# BLDC_Gimbal_Top.net
KiCad netlist of a schematic drawn in Altium Designer
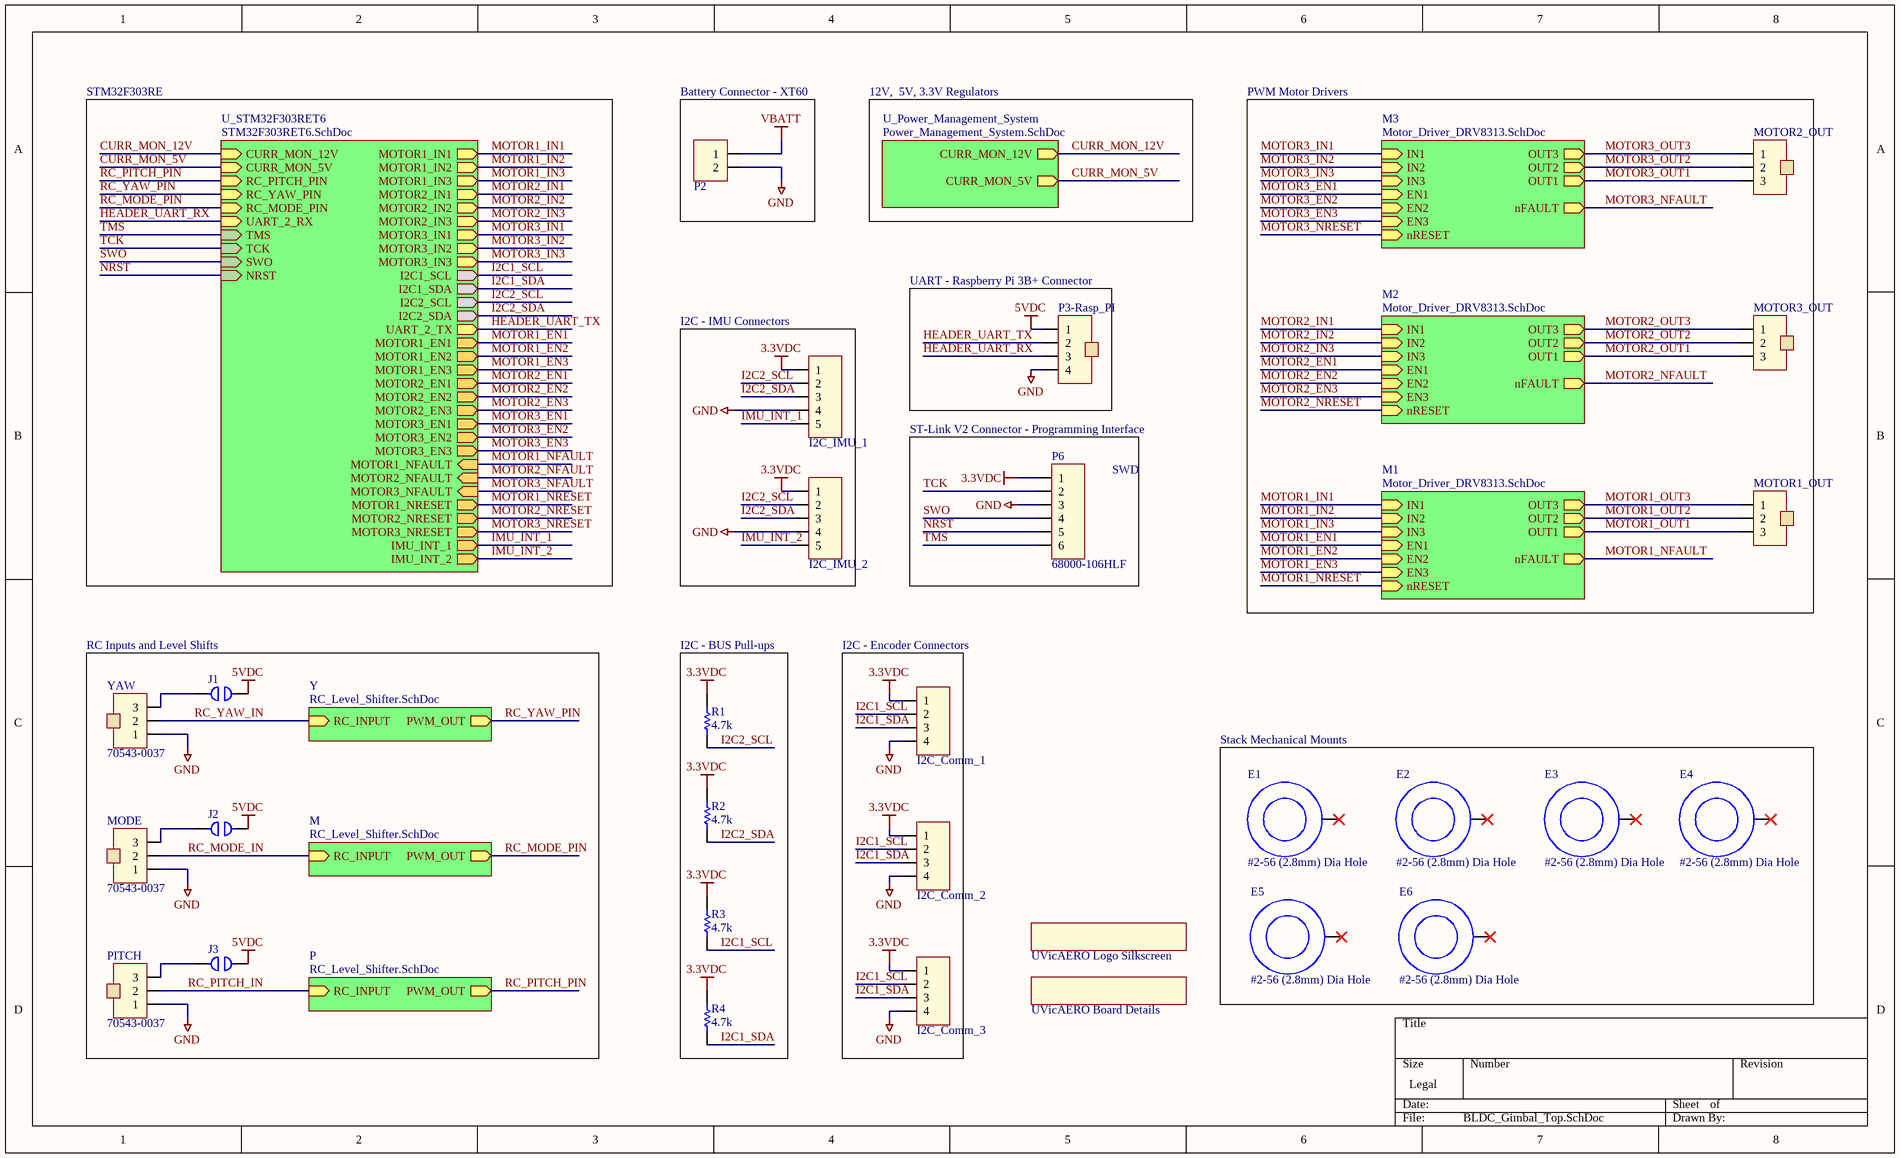
[diagram p0: BLDC_Gimbal_Top.SchDoc]

(export (version "E")
  (design (tool "Eeschema 10.0.6"))
  (components
    (comp (ref "E1")
      (value "#2-56 (2.8mm) Dia Hole")
      (footprint "2-56, Mounting Hole")
      (description "#2-56, with Pin, Mounting Hole")
      (fields (field (name "PUBLISHER") "UVic AERO, KCMR"))
      (libsource (lib "AERO Integrated Library - Miscellaneous") (part "#2-56, w-Pin, Mounting Hole"))
    )
    (comp (ref "E2")
      (value "#2-56 (2.8mm) Dia Hole")
      (footprint "2-56, Mounting Hole")
      (description "#2-56, with Pin, Mounting Hole")
      (fields (field (name "PUBLISHER") "UVic AERO, KCMR"))
      (libsource (lib "AERO Integrated Library - Miscellaneous") (part "#2-56, w-Pin, Mounting Hole"))
    )
    (comp (ref "E3")
      (value "#2-56 (2.8mm) Dia Hole")
      (footprint "2-56, Mounting Hole")
      (description "#2-56, with Pin, Mounting Hole")
      (fields (field (name "PUBLISHER") "UVic AERO, KCMR"))
      (libsource (lib "AERO Integrated Library - Miscellaneous") (part "#2-56, w-Pin, Mounting Hole"))
    )
    (comp (ref "E4")
      (value "#2-56 (2.8mm) Dia Hole")
      (footprint "2-56, Mounting Hole")
      (description "#2-56, with Pin, Mounting Hole")
      (fields (field (name "PUBLISHER") "UVic AERO, KCMR"))
      (libsource (lib "AERO Integrated Library - Miscellaneous") (part "#2-56, w-Pin, Mounting Hole"))
    )
    (comp (ref "E5")
      (value "#2-56 (2.8mm) Dia Hole")
      (footprint "2-56, Mounting Hole")
      (description "#2-56, with Pin, Mounting Hole")
      (fields (field (name "PUBLISHER") "UVic AERO, KCMR"))
      (libsource (lib "AERO Integrated Library - Miscellaneous") (part "#2-56, w-Pin, Mounting Hole"))
    )
    (comp (ref "E6")
      (value "#2-56 (2.8mm) Dia Hole")
      (footprint "2-56, Mounting Hole")
      (description "#2-56, with Pin, Mounting Hole")
      (fields (field (name "PUBLISHER") "UVic AERO, KCMR"))
      (libsource (lib "AERO Integrated Library - Miscellaneous") (part "#2-56, w-Pin, Mounting Hole"))
    )
    (comp (ref "I2C_Comm_1")
      (value "B4B-ZR-SM4-TF(LF)(SN)")
      (footprint "1x4-PIN ZH 1.5mm Pitch")
      (description "Conn Shrouded Header HDR 4 POS 1.5mm Solder ST SMD T/R")
      (fields (field (name "MANUFACTURER") "JST"))
      (libsource (lib "BLDC_Gimbal_Prototype_Lib") (part "B4B-ZR-SM4-TF(LF)(SN)"))
    )
    (comp (ref "I2C_Comm_2")
      (value "B4B-ZR-SM4-TF(LF)(SN)")
      (footprint "1x4-PIN ZH 1.5mm Pitch")
      (description "Conn Shrouded Header HDR 4 POS 1.5mm Solder ST SMD T/R")
      (fields (field (name "MANUFACTURER") "JST"))
      (libsource (lib "BLDC_Gimbal_Prototype_Lib") (part "B4B-ZR-SM4-TF(LF)(SN)"))
    )
    (comp (ref "I2C_Comm_3")
      (value "B4B-ZR-SM4-TF(LF)(SN)")
      (footprint "1x4-PIN ZH 1.5mm Pitch")
      (description "Conn Shrouded Header HDR 4 POS 1.5mm Solder ST SMD T/R")
      (fields (field (name "MANUFACTURER") "JST"))
      (libsource (lib "BLDC_Gimbal_Prototype_Lib") (part "B4B-ZR-SM4-TF(LF)(SN)"))
    )
    (comp (ref "I2C_IMU_1")
      (value "B5B-ZR-SM4-TF(LF)(SN)")
      (footprint "1x5-PIN ZH 1.5mm Pitch")
      (description "CONN HEADER ZH TOP 5POS 1.5MM")
      (fields (field (name "MANUFACTURER") "JST"))
      (libsource (lib "BLDC_Gimbal_Prototype_Lib") (part "B5B-ZR-SM4-TF(LF)(SN)"))
    )
    (comp (ref "I2C_IMU_2")
      (value "B5B-ZR-SM4-TF(LF)(SN)")
      (footprint "1x5-PIN ZH 1.5mm Pitch")
      (description "CONN HEADER ZH TOP 5POS 1.5MM")
      (fields (field (name "MANUFACTURER") "JST"))
      (libsource (lib "BLDC_Gimbal_Prototype_Lib") (part "B5B-ZR-SM4-TF(LF)(SN)"))
    )
    (comp (ref "J1")
      (value "3M9580-ND")
      (footprint "Jumper-2Pin, THT")
      (description "Jumper, 0.1\" (2.54mm), Gold, THT, 68001-202HLF & 3M9580-ND")
      (fields
        (field (name "MFG") "FCI")
        (field (name "PUBLISHER") "UVic AERO, Kirk Richardson")
        (field (name "REVIEWEDBY") "*")
      )
      (libsource (lib "AERO Schematic Library - Miscellaneous") (part "Jumper, 0.1{dblquote} (2.54mm), Gold, THT, 68001-202HLF"))
    )
    (comp (ref "J2")
      (value "3M9580-ND")
      (footprint "Jumper-2Pin, THT")
      (description "Jumper, 0.1\" (2.54mm), Gold, THT, 68001-202HLF & 3M9580-ND")
      (fields
        (field (name "MFG") "FCI")
        (field (name "PUBLISHER") "UVic AERO, Kirk Richardson")
        (field (name "REVIEWEDBY") "*")
      )
      (libsource (lib "AERO Schematic Library - Miscellaneous") (part "Jumper, 0.1{dblquote} (2.54mm), Gold, THT, 68001-202HLF"))
    )
    (comp (ref "J3")
      (value "3M9580-ND")
      (footprint "Jumper-2Pin, THT")
      (description "Jumper, 0.1\" (2.54mm), Gold, THT, 68001-202HLF & 3M9580-ND")
      (fields
        (field (name "MFG") "FCI")
        (field (name "PUBLISHER") "UVic AERO, Kirk Richardson")
        (field (name "REVIEWEDBY") "*")
      )
      (libsource (lib "AERO Schematic Library - Miscellaneous") (part "Jumper, 0.1{dblquote} (2.54mm), Gold, THT, 68001-202HLF"))
    )
    (comp (ref "LB1")
      (value "UVicAERO Board Details")
      (footprint "UVicAERO, Board Details, Silkscreen")
      (description "Logo, UVic AERO, Board Details, Silkscreen")
      (fields (field (name "PUBLISHER") "UVic AERO, KCMR"))
      (libsource (lib "AERO Schematic Library - Miscellaneous") (part "Logo, UVic AERO, Board Details"))
    )
    (comp (ref "LB2")
      (value "UVicAERO Logo Silkscreen")
      (footprint "UVicAERO_Logo, 7mm Width")
      (description "Logo, UVic AERO 2014, 7mm Width, Silkscreen")
      (fields (field (name "PUBLISHER") "UVic AERO, KCMR"))
      (libsource (lib "AERO Schematic Library - Miscellaneous") (part "Logo, UVic AERO 2014, 7mm"))
    )
    (comp (ref "MODE")
      (value "70543-0037")
      (footprint "Header-3Pin, THT, Shrouded")
      (description "1x3-Pin, Pitch: 0.1\" (2.54mm), Tin, THT, Shrouded, Locking, 70543-0037")
      (fields
        (field (name "MFG") "Molex Inc")
        (field (name "PUBLISHER") "UVic AERO, Kirk Richardson")
        (field (name "REVIEWEDBY") "Matthew Fitz")
        (field (name "REVIEWEDNOTE") "There should be tin pins instead of gold")
      )
      (libsource (lib "AERO Schematic Library - Connectors") (part "1x3-Pin, Pitch{colon} 0.1{dblquote} (2.54mm), Tin, THT, Shrouded, Locking, 70543-0037"))
    )
    (comp (ref "MOTOR1_OUT")
      (value "70543-0037")
      (footprint "Header-3Pin, THT, Shrouded")
      (description "1x3-Pin, Pitch: 0.1\" (2.54mm), Tin, THT, Shrouded, Locking, 70543-0037")
      (fields
        (field (name "MFG") "Molex Inc")
        (field (name "PUBLISHER") "UVic AERO, Kirk Richardson")
        (field (name "REVIEWEDBY") "Matthew Fitz")
        (field (name "REVIEWEDNOTE") "There should be tin pins instead of gold")
      )
      (libsource (lib "") (part "1x3-Pin, Pitch{colon} 0.1{dblquote} (2.54mm), Tin, THT, Shrouded, Locking, 70543-0037_1"))
    )
    (comp (ref "MOTOR2_OUT")
      (value "70543-0037")
      (footprint "Header-3Pin, THT, Shrouded")
      (description "1x3-Pin, Pitch: 0.1\" (2.54mm), Tin, THT, Shrouded, Locking, 70543-0037")
      (fields
        (field (name "MFG") "Molex Inc")
        (field (name "PUBLISHER") "UVic AERO, Kirk Richardson")
        (field (name "REVIEWEDBY") "Matthew Fitz")
        (field (name "REVIEWEDNOTE") "There should be tin pins instead of gold")
      )
      (libsource (lib "") (part "1x3-Pin, Pitch{colon} 0.1{dblquote} (2.54mm), Tin, THT, Shrouded, Locking, 70543-0037_1"))
    )
    (comp (ref "MOTOR3_OUT")
      (value "70543-0037")
      (footprint "Header-3Pin, THT, Shrouded")
      (description "1x3-Pin, Pitch: 0.1\" (2.54mm), Tin, THT, Shrouded, Locking, 70543-0037")
      (fields
        (field (name "MFG") "Molex Inc")
        (field (name "PUBLISHER") "UVic AERO, Kirk Richardson")
        (field (name "REVIEWEDBY") "Matthew Fitz")
        (field (name "REVIEWEDNOTE") "There should be tin pins instead of gold")
      )
      (libsource (lib "") (part "1x3-Pin, Pitch{colon} 0.1{dblquote} (2.54mm), Tin, THT, Shrouded, Locking, 70543-0037_1"))
    )
    (comp (ref "P2")
      (value "2x1-Pin, Pitch: 3.00mm, Battery Connector")
      (footprint "XT60")
      (description "XT60 - 2x1-Pin, Pitch: 3.00mm, Battery Connector")
      (fields (field (name "PUBLISHER") "UVic AERO, Luke Mills") (field (name "REVIEWEDBY") "*"))
      (libsource (lib "BLDC_Gimbal_Lib") (part "2x1-Pin, Pitch{colon} 3.00mm, Battery Connector"))
    )
    (comp (ref "P3-Rasp_PI")
      (value "43045-0412")
      (footprint "Header-4Pin, 2x2, THT, Locking, Tin")
      (description "2x2-Pin, Pitch: 3.00mm, Tin, THT, Shrouded, Locking, 43045-0412")
      (fields
        (field (name "MFG") "Molex")
        (field (name "PUBLISHER") "UVic AERO, Taylor Eby")
        (field (name "REVIEWEDBY") "Kirk Richardson")
      )
      (libsource (lib "AERO Schematic Library - Connectors") (part "2x2-Pin, Pitch{colon} 3.00mm, Tin, THT, 43045-0412"))
    )
    (comp (ref "P6")
      (value "68000-106HLF")
      (footprint "Header-6Pin, THT")
      (description "Header, 1x6-Pin, Pitch: 0.1\" (2.54mm), Gold 30µin, THT, 68000-106HLF")
      (fields
        (field (name "MFG") "FCI")
        (field (name "PUBLISHER") "UVic AERO, Kirk Richardson")
        (field (name "REVIEWEDBY") "*")
      )
      (libsource (lib "AERO Integrated Library - Connectors") (part "Header, 1x6-Pin, Pitch{colon} 0.1{dblquote} (2.54mm), Gold 30µin, THT, 68000-106HLF"))
    )
    (comp (ref "PITCH")
      (value "70543-0037")
      (footprint "Header-3Pin, THT, Shrouded")
      (description "1x3-Pin, Pitch: 0.1\" (2.54mm), Tin, THT, Shrouded, Locking, 70543-0037")
      (fields
        (field (name "MFG") "Molex Inc")
        (field (name "PUBLISHER") "UVic AERO, Kirk Richardson")
        (field (name "REVIEWEDBY") "Matthew Fitz")
        (field (name "REVIEWEDNOTE") "There should be tin pins instead of gold")
      )
      (libsource (lib "AERO Schematic Library - Connectors") (part "1x3-Pin, Pitch{colon} 0.1{dblquote} (2.54mm), Tin, THT, Shrouded, Locking, 70543-0037"))
    )
    (comp (ref "R1")
      (value "4.7k")
      (footprint "RESC2012N(0805\")")
      (description "RES SMD 4.7k ohm, 150 V, 0805 [2012 Metric], 250 mW,  1%")
      (fields
        (field (name "MANUFACTURER") "Yageo")
        (field (name "MANUFACTURER PART NUMBER") "RC0805FR-074K7L")
      )
      (libsource (lib "BLDC_Gimbal_Prototype_Lib") (part "RC0805FR-074K7L"))
    )
    (comp (ref "R2")
      (value "4.7k")
      (footprint "RESC2012N(0805\")")
      (description "RES SMD 4.7k ohm, 150 V, 0805 [2012 Metric], 250 mW,  1%")
      (fields
        (field (name "MANUFACTURER") "Yageo")
        (field (name "MANUFACTURER PART NUMBER") "RC0805FR-074K7L")
      )
      (libsource (lib "BLDC_Gimbal_Prototype_Lib") (part "RC0805FR-074K7L"))
    )
    (comp (ref "R3")
      (value "4.7k")
      (footprint "RESC2012N(0805\")")
      (description "RES SMD 4.7k ohm, 150 V, 0805 [2012 Metric], 250 mW,  1%")
      (fields
        (field (name "MANUFACTURER") "Yageo")
        (field (name "MANUFACTURER PART NUMBER") "RC0805FR-074K7L")
      )
      (libsource (lib "BLDC_Gimbal_Prototype_Lib") (part "RC0805FR-074K7L"))
    )
    (comp (ref "R4")
      (value "4.7k")
      (footprint "RESC2012N(0805\")")
      (description "RES SMD 4.7k ohm, 150 V, 0805 [2012 Metric], 250 mW,  1%")
      (fields
        (field (name "MANUFACTURER") "Yageo")
        (field (name "MANUFACTURER PART NUMBER") "RC0805FR-074K7L")
      )
      (libsource (lib "BLDC_Gimbal_Prototype_Lib") (part "RC0805FR-074K7L"))
    )
    (comp (ref "YAW")
      (value "70543-0037")
      (footprint "Header-3Pin, THT, Shrouded")
      (description "1x3-Pin, Pitch: 0.1\" (2.54mm), Tin, THT, Shrouded, Locking, 70543-0037")
      (fields
        (field (name "MFG") "Molex Inc")
        (field (name "PUBLISHER") "UVic AERO, Kirk Richardson")
        (field (name "REVIEWEDBY") "Matthew Fitz")
        (field (name "REVIEWEDNOTE") "There should be tin pins instead of gold")
      )
      (libsource (lib "AERO Schematic Library - Connectors") (part "1x3-Pin, Pitch{colon} 0.1{dblquote} (2.54mm), Tin, THT, Shrouded, Locking, 70543-0037"))
    )
  )
  (nets
    (net (code "3") (name "/HEADER_UART_RX") (class "Default")
      (node (ref "P3-Rasp_PI") (pin "3") (pinfunction "3_3") (pintype "passive"))
    )
    (net (code "4") (name "/HEADER_UART_TX") (class "Default")
      (node (ref "P3-Rasp_PI") (pin "2") (pinfunction "2_2") (pintype "passive"))
    )
    (net (code "5") (name "/I2C1_SCL") (class "Default")
      (node (ref "I2C_Comm_1") (pin "2") (pinfunction "2_2") (pintype "passive"))
      (node (ref "I2C_Comm_2") (pin "2") (pinfunction "2_2") (pintype "passive"))
      (node (ref "I2C_Comm_3") (pin "2") (pinfunction "2_2") (pintype "passive"))
      (node (ref "R3") (pin "1") (pinfunction "1_1") (pintype "passive"))
    )
    (net (code "6") (name "/I2C1_SDA") (class "Default")
      (node (ref "I2C_Comm_1") (pin "3") (pinfunction "3_3") (pintype "passive"))
      (node (ref "I2C_Comm_2") (pin "3") (pinfunction "3_3") (pintype "passive"))
      (node (ref "I2C_Comm_3") (pin "3") (pinfunction "3_3") (pintype "passive"))
      (node (ref "R4") (pin "1") (pinfunction "1_1") (pintype "passive"))
    )
    (net (code "7") (name "/I2C2_SCL") (class "Default")
      (node (ref "I2C_IMU_1") (pin "2") (pinfunction "2_2") (pintype "passive"))
      (node (ref "I2C_IMU_2") (pin "2") (pinfunction "2_2") (pintype "passive"))
      (node (ref "R1") (pin "1") (pinfunction "1_1") (pintype "passive"))
    )
    (net (code "8") (name "/I2C2_SDA") (class "Default")
      (node (ref "I2C_IMU_1") (pin "3") (pinfunction "3_3") (pintype "passive"))
      (node (ref "I2C_IMU_2") (pin "3") (pinfunction "3_3") (pintype "passive"))
      (node (ref "R2") (pin "1") (pinfunction "1_1") (pintype "passive"))
    )
    (net (code "9") (name "/IMU_INT_1") (class "Default")
      (node (ref "I2C_IMU_1") (pin "5") (pinfunction "5_5") (pintype "passive"))
    )
    (net (code "10") (name "/IMU_INT_2") (class "Default")
      (node (ref "I2C_IMU_2") (pin "5") (pinfunction "5_5") (pintype "passive"))
    )
    (net (code "19") (name "/MOTOR1_OUT1") (class "Default")
      (node (ref "MOTOR1_OUT") (pin "3") (pinfunction "3_3") (pintype "passive"))
    )
    (net (code "20") (name "/MOTOR1_OUT2") (class "Default")
      (node (ref "MOTOR1_OUT") (pin "2") (pinfunction "2_2") (pintype "passive"))
    )
    (net (code "21") (name "/MOTOR1_OUT3") (class "Default")
      (node (ref "MOTOR1_OUT") (pin "1") (pinfunction "1_1") (pintype "passive"))
    )
    (net (code "30") (name "/MOTOR2_OUT1") (class "Default")
      (node (ref "MOTOR3_OUT") (pin "3") (pinfunction "3_3") (pintype "passive"))
    )
    (net (code "31") (name "/MOTOR2_OUT2") (class "Default")
      (node (ref "MOTOR3_OUT") (pin "2") (pinfunction "2_2") (pintype "passive"))
    )
    (net (code "32") (name "/MOTOR2_OUT3") (class "Default")
      (node (ref "MOTOR3_OUT") (pin "1") (pinfunction "1_1") (pintype "passive"))
    )
    (net (code "41") (name "/MOTOR3_OUT1") (class "Default")
      (node (ref "MOTOR2_OUT") (pin "3") (pinfunction "3_3") (pintype "passive"))
    )
    (net (code "42") (name "/MOTOR3_OUT2") (class "Default")
      (node (ref "MOTOR2_OUT") (pin "2") (pinfunction "2_2") (pintype "passive"))
    )
    (net (code "43") (name "/MOTOR3_OUT3") (class "Default")
      (node (ref "MOTOR2_OUT") (pin "1") (pinfunction "1_1") (pintype "passive"))
    )
    (net (code "44") (name "/NRST") (class "Default")
      (node (ref "P6") (pin "5") (pinfunction "5_5") (pintype "passive"))
    )
    (net (code "45") (name "/RC_MODE_IN") (class "Default")
      (node (ref "MODE") (pin "2") (pinfunction "2_2") (pintype "passive"))
    )
    (net (code "47") (name "/RC_PITCH_IN") (class "Default")
      (node (ref "PITCH") (pin "2") (pinfunction "2_2") (pintype "passive"))
    )
    (net (code "49") (name "/RC_YAW_IN") (class "Default")
      (node (ref "YAW") (pin "2") (pinfunction "2_2") (pintype "passive"))
    )
    (net (code "51") (name "/SWO") (class "Default")
      (node (ref "P6") (pin "4") (pinfunction "4_4") (pintype "passive"))
    )
    (net (code "52") (name "/TCK") (class "Default")
      (node (ref "P6") (pin "2") (pinfunction "2_2") (pintype "passive"))
    )
    (net (code "53") (name "/TMS") (class "Default")
      (node (ref "P6") (pin "6") (pinfunction "6_6") (pintype "passive"))
    )
    (net (code "54") (name "3.3VDC") (class "Default")
      (node (ref "I2C_Comm_1") (pin "1") (pinfunction "1_1") (pintype "passive"))
      (node (ref "I2C_Comm_2") (pin "1") (pinfunction "1_1") (pintype "passive"))
      (node (ref "I2C_Comm_3") (pin "1") (pinfunction "1_1") (pintype "passive"))
      (node (ref "I2C_IMU_1") (pin "1") (pinfunction "1_1") (pintype "passive"))
      (node (ref "I2C_IMU_2") (pin "1") (pinfunction "1_1") (pintype "passive"))
      (node (ref "P6") (pin "1") (pinfunction "1_1") (pintype "passive"))
      (node (ref "R1") (pin "2") (pinfunction "2_2") (pintype "passive"))
      (node (ref "R2") (pin "2") (pinfunction "2_2") (pintype "passive"))
      (node (ref "R3") (pin "2") (pinfunction "2_2") (pintype "passive"))
      (node (ref "R4") (pin "2") (pinfunction "2_2") (pintype "passive"))
    )
    (net (code "55") (name "5VDC") (class "Default")
      (node (ref "J1") (pin "2") (pinfunction "2_2") (pintype "passive"))
      (node (ref "J2") (pin "2") (pinfunction "2_2") (pintype "passive"))
      (node (ref "J3") (pin "2") (pinfunction "2_2") (pintype "passive"))
      (node (ref "P3-Rasp_PI") (pin "1") (pinfunction "1_1") (pintype "passive"))
    )
    (net (code "56") (name "GND") (class "Default")
      (node (ref "I2C_Comm_1") (pin "4") (pinfunction "4_4") (pintype "passive"))
      (node (ref "I2C_Comm_2") (pin "4") (pinfunction "4_4") (pintype "passive"))
      (node (ref "I2C_Comm_3") (pin "4") (pinfunction "4_4") (pintype "passive"))
      (node (ref "I2C_IMU_1") (pin "4") (pinfunction "4_4") (pintype "passive"))
      (node (ref "I2C_IMU_2") (pin "4") (pinfunction "4_4") (pintype "passive"))
      (node (ref "MODE") (pin "1") (pinfunction "1_1") (pintype "passive"))
      (node (ref "P2") (pin "2") (pinfunction "2_2") (pintype "passive"))
      (node (ref "P3-Rasp_PI") (pin "4") (pinfunction "4_4") (pintype "passive"))
      (node (ref "P6") (pin "3") (pinfunction "3_3") (pintype "passive"))
      (node (ref "PITCH") (pin "1") (pinfunction "1_1") (pintype "passive"))
      (node (ref "YAW") (pin "1") (pinfunction "1_1") (pintype "passive"))
    )
    (net (code "57") (name "Net-(J1-Pad1)") (class "Default")
      (node (ref "J1") (pin "1") (pinfunction "1_1") (pintype "passive"))
      (node (ref "YAW") (pin "3") (pinfunction "3_3") (pintype "passive"))
    )
    (net (code "58") (name "Net-(J2-Pad1)") (class "Default")
      (node (ref "J2") (pin "1") (pinfunction "1_1") (pintype "passive"))
      (node (ref "MODE") (pin "3") (pinfunction "3_3") (pintype "passive"))
    )
    (net (code "59") (name "Net-(J3-Pad1)") (class "Default")
      (node (ref "J3") (pin "1") (pinfunction "1_1") (pintype "passive"))
      (node (ref "PITCH") (pin "3") (pinfunction "3_3") (pintype "passive"))
    )
    (net (code "60") (name "VBATT") (class "Default")
      (node (ref "P2") (pin "1") (pinfunction "1_1") (pintype "passive"))
    )
    (net (code "61") (name "unconnected-(E1-Pad0)") (class "Default")
      (node (ref "E1") (pin "0") (pinfunction "0_0") (pintype "passive+no_connect"))
    )
    (net (code "62") (name "unconnected-(E2-Pad0)") (class "Default")
      (node (ref "E2") (pin "0") (pinfunction "0_0") (pintype "passive+no_connect"))
    )
    (net (code "63") (name "unconnected-(E3-Pad0)") (class "Default")
      (node (ref "E3") (pin "0") (pinfunction "0_0") (pintype "passive+no_connect"))
    )
    (net (code "64") (name "unconnected-(E4-Pad0)") (class "Default")
      (node (ref "E4") (pin "0") (pinfunction "0_0") (pintype "passive+no_connect"))
    )
    (net (code "65") (name "unconnected-(E5-Pad0)") (class "Default")
      (node (ref "E5") (pin "0") (pinfunction "0_0") (pintype "passive+no_connect"))
    )
    (net (code "66") (name "unconnected-(E6-Pad0)") (class "Default")
      (node (ref "E6") (pin "0") (pinfunction "0_0") (pintype "passive+no_connect"))
    )
  )
)
